# POTENCIA.net
KiCad netlist of a schematic drawn in Altium Designer
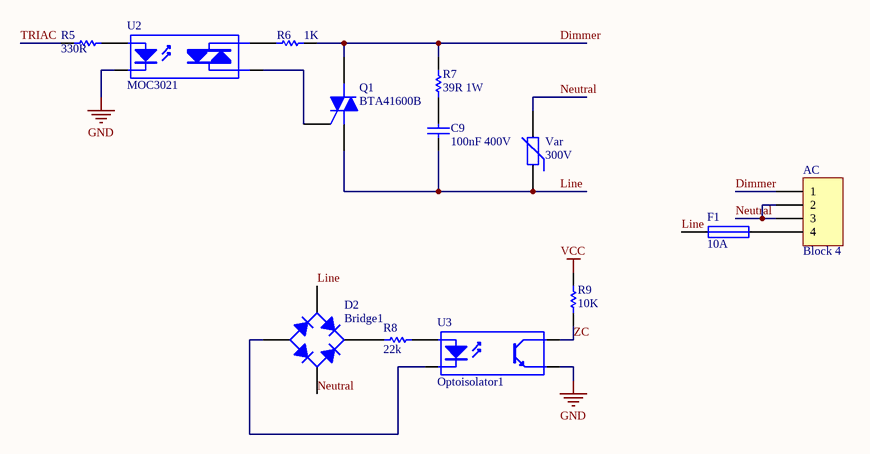
[diagram p0: POTENCIA.SchDoc]

(export (version "E")
  (design (tool "Eeschema 10.0.6"))
  (components
    (comp (ref "AC")
      (value "Block 4")
      (footprint "BOR-4-7.5")
      (description "Header, 4-Pin")
      (fields (field (name "PUBLISHER") "Altium Limited"))
      (libsource (lib "Miscellaneous Connectors") (part "Header 4"))
    )
    (comp (ref "C9")
      (value "100nF 400V")
      (footprint "RAD-0.4")
      (description "Capacitor")
      (fields (field (name "PUBLISHER") "Altium Limited"))
      (libsource (lib "Miscellaneous Devices") (part "Cap"))
    )
    (comp (ref "D2")
      (value "Bridge1")
      (footprint "DF1502S-T")
      (description "Full Wave Diode Bridge")
      (fields (field (name "PUBLISHER") "Altium Limited"))
      (libsource (lib "Miscellaneous Devices") (part "Bridge1"))
    )
    (comp (ref "F1")
      (value "10A")
      (footprint "FUSE HOLDER")
      (description "Fuse")
      (fields (field (name "PUBLISHER") "Altium Limited"))
      (libsource (lib "Miscellaneous Devices") (part "Fuse 1"))
    )
    (comp (ref "Q1")
      (value "BTA41600B")
      (footprint "TOP3 SINKED")
      (description "Silicon Bidirectional Triode Thyristor")
      (libsource (lib "Miscellaneous Devices") (part "Triac"))
    )
    (comp (ref "R5")
      (value "330R")
      (footprint "CR3216-1206")
      (description "Resistor")
      (libsource (lib "Miscellaneous Devices") (part "Res1"))
    )
    (comp (ref "R6")
      (value "1K")
      (footprint "CR3216-1206")
      (description "Resistor")
      (fields (field (name "Comment") "1k"))
      (libsource (lib "Miscellaneous Devices") (part "Res1"))
    )
    (comp (ref "R7")
      (value "39R 1W")
      (footprint "AXIAL- 1W")
      (description "Resistor")
      (libsource (lib "Miscellaneous Devices") (part "Res1"))
    )
    (comp (ref "R8")
      (value "22k")
      (footprint "AXIAL-0.4")
      (description "Resistor")
      (libsource (lib "Miscellaneous Devices") (part "Res1"))
    )
    (comp (ref "R9")
      (value "10K")
      (footprint "6-0805_N")
      (description "Resistor")
      (libsource (lib "Miscellaneous Devices") (part "Res1"))
    )
    (comp (ref "U2") (value "MOC3021") (footprint "DIP-6") (libsource (lib "ESQUEMATICOS") (part "MOC3021")))
    (comp (ref "U3")
      (value "Optoisolator1")
      (footprint "DIP-4")
      (description "4-Pin Phototransistor Optocoupler")
      (fields (field (name "PUBLISHER") "Altium Limited"))
      (libsource (lib "Miscellaneous Devices") (part "Optoisolator1"))
    )
    (comp (ref "Var")
      (value "300V")
      (footprint "S20K115")
      (description "Varistor (Voltage-Sensitive Resistor)")
      (fields (field (name "PUBLISHER") "Altium Limited"))
      (libsource (lib "Miscellaneous Devices") (part "Res Varistor"))
    )
  )
  (nets
    (net (code "1") (name "/Dimmer") (class "Default")
      (node (ref "AC") (pin "1") (pinfunction "1_1") (pintype "passive"))
      (node (ref "Q1") (pin "2") (pinfunction "M2_2") (pintype "passive"))
      (node (ref "R6") (pin "2") (pinfunction "2_2") (pintype "passive"))
      (node (ref "R7") (pin "2") (pinfunction "2_2") (pintype "passive"))
    )
    (net (code "2") (name "/Line") (class "Default")
      (node (ref "C9") (pin "1") (pinfunction "1_1") (pintype "passive"))
      (node (ref "D2") (pin "4") (pinfunction "C_4") (pintype "passive"))
      (node (ref "F1") (pin "1") (pinfunction "1_1") (pintype "passive"))
      (node (ref "Q1") (pin "1") (pinfunction "M1_1") (pintype "passive"))
      (node (ref "Var") (pin "1") (pinfunction "1_1") (pintype "passive"))
    )
    (net (code "3") (name "/Neutral") (class "Default")
      (node (ref "AC") (pin "2") (pinfunction "2_2") (pintype "passive"))
      (node (ref "AC") (pin "3") (pinfunction "3_3") (pintype "passive"))
      (node (ref "D2") (pin "2") (pinfunction "C_2") (pintype "passive"))
      (node (ref "Var") (pin "2") (pinfunction "2_2") (pintype "passive"))
    )
    (net (code "4") (name "/TRIAC") (class "Default")
      (node (ref "R5") (pin "1") (pinfunction "1_1") (pintype "passive"))
    )
    (net (code "5") (name "/ZC") (class "Default")
      (node (ref "R9") (pin "1") (pinfunction "1_1") (pintype "passive"))
      (node (ref "U3") (pin "4") (pinfunction "C_4") (pintype "passive"))
    )
    (net (code "6") (name "GND") (class "Default")
      (node (ref "U2") (pin "2") (pinfunction "K_2") (pintype "passive"))
      (node (ref "U3") (pin "3") (pinfunction "E_3") (pintype "passive"))
    )
    (net (code "7") (name "Net-(AC-Pad4)") (class "Default")
      (node (ref "AC") (pin "4") (pinfunction "4_4") (pintype "passive"))
      (node (ref "F1") (pin "2") (pinfunction "2_2") (pintype "passive"))
    )
    (net (code "8") (name "Net-(C9-Pad2)") (class "Default")
      (node (ref "C9") (pin "2") (pinfunction "2_2") (pintype "passive"))
      (node (ref "R7") (pin "1") (pinfunction "1_1") (pintype "passive"))
    )
    (net (code "9") (name "Net-(D2-A)") (class "Default")
      (node (ref "D2") (pin "3") (pinfunction "A_3") (pintype "passive"))
      (node (ref "U3") (pin "2") (pinfunction "K_2") (pintype "passive"))
    )
    (net (code "10") (name "Net-(D2-K)") (class "Default")
      (node (ref "D2") (pin "1") (pinfunction "K_1") (pintype "passive"))
      (node (ref "R8") (pin "2") (pinfunction "2_2") (pintype "passive"))
    )
    (net (code "11") (name "Net-(Q1-G)") (class "Default")
      (node (ref "Q1") (pin "3") (pinfunction "G_3") (pintype "passive"))
      (node (ref "U2") (pin "4") (pinfunction "A/K_4") (pintype "passive"))
    )
    (net (code "12") (name "Net-(R6-Pad1)") (class "Default")
      (node (ref "R6") (pin "1") (pinfunction "1_1") (pintype "passive"))
      (node (ref "U2") (pin "6") (pinfunction "A/K_6") (pintype "passive"))
    )
    (net (code "13") (name "Net-(U2-A)") (class "Default")
      (node (ref "R5") (pin "2") (pinfunction "2_2") (pintype "passive"))
      (node (ref "U2") (pin "1") (pinfunction "A_1") (pintype "passive"))
    )
    (net (code "14") (name "Net-(U3-A)") (class "Default")
      (node (ref "R8") (pin "1") (pinfunction "1_1") (pintype "passive"))
      (node (ref "U3") (pin "1") (pinfunction "A_1") (pintype "passive"))
    )
    (net (code "15") (name "VCC") (class "Default")
      (node (ref "R9") (pin "2") (pinfunction "2_2") (pintype "passive"))
    )
  )
)
